# 0_3d.net
KiCad netlist of a schematic drawn in EAGLE
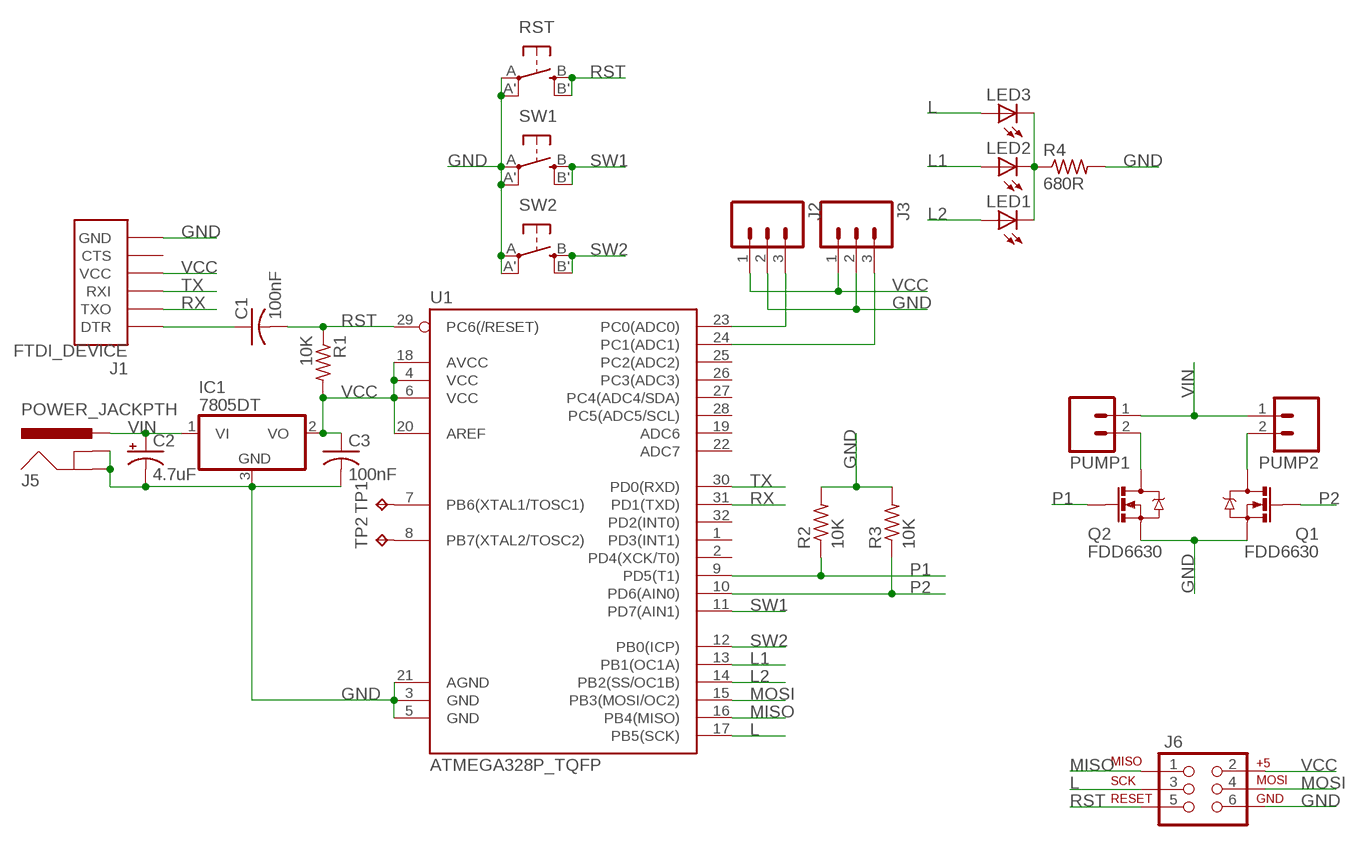
[diagram p0: schematic, sheet 1]

(export (version "E")
  (design (tool "Eeschema 10.0.6"))
  (components
    (comp (ref "C1")
      (value "100nF")
      (footprint "eagle-import:C1206K")
      (libsource (lib "eagle-import") (part "resistor_C-USC1206K"))
    )
    (comp (ref "C2")
      (value "4.7uF")
      (footprint "eagle-import:153CLV-0405")
      (libsource (lib "eagle-import") (part "CPOL-US153CLV-0405"))
    )
    (comp (ref "C3")
      (value "100nF")
      (footprint "eagle-import:C1206K")
      (libsource (lib "eagle-import") (part "C-USC1206K"))
    )
    (comp (ref "IC1")
      (value "7805DT")
      (footprint "eagle-import:TO252")
      (libsource (lib "eagle-import") (part "78DT05"))
    )
    (comp (ref "J1")
      (value "FTDI_DEVICE")
      (footprint "eagle-import:FTDI_DEVICE_SIDE")
      (libsource (lib "eagle-import") (part "FTDI_DEVICE"))
    )
    (comp (ref "J2")
      (value "M03PTH")
      (footprint "eagle-import:1X03")
      (libsource (lib "eagle-import") (part "M03PTH"))
    )
    (comp (ref "J3")
      (value "M03PTH")
      (footprint "eagle-import:1X03")
      (libsource (lib "eagle-import") (part "M03PTH"))
    )
    (comp (ref "J5")
      (value "POWER_JACKPTH")
      (footprint "eagle-import:POWER_JACK_PTH")
      (libsource (lib "eagle-import") (part "POWER_JACKPTH"))
    )
    (comp (ref "J6")
      (value "AVR_SPI_PRG_6PTH")
      (footprint "eagle-import:2X3")
      (libsource (lib "eagle-import") (part "AVR_SPI_PRG_6PTH"))
    )
    (comp (ref "LED1")
      (value "LED3MM")
      (footprint "eagle-import:LED3MM")
      (libsource (lib "eagle-import") (part "LED3MM"))
    )
    (comp (ref "LED2")
      (value "LED3MM")
      (footprint "eagle-import:LED3MM")
      (libsource (lib "eagle-import") (part "LED3MM"))
    )
    (comp (ref "LED3")
      (value "LED3MM")
      (footprint "eagle-import:LED3MM")
      (libsource (lib "eagle-import") (part "LED3MM"))
    )
    (comp (ref "PUMP1")
      (value "M02PTH")
      (footprint "eagle-import:1X02")
      (libsource (lib "eagle-import") (part "M02PTH"))
    )
    (comp (ref "PUMP2")
      (value "M02PTH")
      (footprint "eagle-import:1X02")
      (libsource (lib "eagle-import") (part "M02PTH"))
    )
    (comp (ref "Q1")
      (value "FDD6630")
      (footprint "eagle-import:D-PAK_TO252AA")
      (libsource (lib "eagle-import") (part "MOSFET-NCHANNEL_D-PAK"))
    )
    (comp (ref "Q2")
      (value "FDD6630")
      (footprint "eagle-import:D-PAK_TO252AA")
      (libsource (lib "eagle-import") (part "MOSFET-NCHANNEL_D-PAK"))
    )
    (comp (ref "R1")
      (value "10K")
      (footprint "eagle-import:M0805")
      (libsource (lib "eagle-import") (part "R-US_M0805"))
    )
    (comp (ref "R2")
      (value "10K")
      (footprint "eagle-import:M0805")
      (libsource (lib "eagle-import") (part "R-US_M0805"))
    )
    (comp (ref "R3")
      (value "10K")
      (footprint "eagle-import:M0805")
      (libsource (lib "eagle-import") (part "R-US_M0805"))
    )
    (comp (ref "R4")
      (value "680R")
      (footprint "eagle-import:M0805")
      (libsource (lib "eagle-import") (part "R-US_M0805"))
    )
    (comp (ref "RST")
      (value "SPST_TACT-EVQQ2")
      (footprint "eagle-import:EVQ-Q2")
      (libsource (lib "eagle-import") (part "SPST_TACT-EVQQ2"))
    )
    (comp (ref "SW1")
      (value "SPST_TACT-EVQQ2")
      (footprint "eagle-import:EVQ-Q2")
      (libsource (lib "eagle-import") (part "SPST_TACT-EVQQ2"))
    )
    (comp (ref "SW2")
      (value "SPST_TACT-EVQQ2")
      (footprint "eagle-import:EVQ-Q2")
      (libsource (lib "eagle-import") (part "SPST_TACT-EVQQ2"))
    )
    (comp (ref "TP1")
      (value "TPTP15SQ")
      (footprint "eagle-import:TP15SQ")
      (libsource (lib "eagle-import") (part "TPTP15SQ"))
    )
    (comp (ref "TP2")
      (value "TPTP15SQ")
      (footprint "eagle-import:TP15SQ")
      (libsource (lib "eagle-import") (part "TPTP15SQ"))
    )
    (comp (ref "U1")
      (value "ATMEGA328P_TQFP")
      (footprint "eagle-import:TQFP32-08")
      (libsource (lib "eagle-import") (part "ATMEGA328P_TQFP"))
    )
  )
  (nets
    (net (code "1") (name "/GND") (class "Default")
      (node (ref "C2") (pin "-") (pinfunction "-_-") (pintype "passive"))
      (node (ref "C3") (pin "2") (pinfunction "2_2") (pintype "passive"))
      (node (ref "IC1") (pin "3") (pinfunction "GND_3") (pintype "passive"))
      (node (ref "J1") (pin "P$6") (pinfunction "GND_P$6") (pintype "bidirectional"))
      (node (ref "J2") (pin "2") (pinfunction "2_2") (pintype "passive"))
      (node (ref "J3") (pin "2") (pinfunction "2_2") (pintype "passive"))
      (node (ref "J5") (pin "GND") (pinfunction "GND_GND") (pintype "bidirectional"))
      (node (ref "J5") (pin "GNDBREAK") (pinfunction "GNDBREAK_GNDBREAK") (pintype "bidirectional"))
      (node (ref "J6") (pin "6") (pinfunction "6_6") (pintype "passive"))
      (node (ref "Q1") (pin "3") (pinfunction "S_3") (pintype "passive"))
      (node (ref "Q2") (pin "3") (pinfunction "S_3") (pintype "passive"))
      (node (ref "R2") (pin "2") (pinfunction "2_2") (pintype "passive"))
      (node (ref "R3") (pin "2") (pinfunction "2_2") (pintype "passive"))
      (node (ref "R4") (pin "2") (pinfunction "2_2") (pintype "passive"))
      (node (ref "RST") (pin "A") (pinfunction "P_A") (pintype "passive"))
      (node (ref "RST") (pin "A'") (pinfunction "P1_A'") (pintype "passive"))
      (node (ref "SW1") (pin "A") (pinfunction "P_A") (pintype "passive"))
      (node (ref "SW1") (pin "A'") (pinfunction "P1_A'") (pintype "passive"))
      (node (ref "SW2") (pin "A") (pinfunction "P_A") (pintype "passive"))
      (node (ref "SW2") (pin "A'") (pinfunction "P1_A'") (pintype "passive"))
      (node (ref "U1") (pin "21") (pinfunction "AGND_21") (pintype "bidirectional"))
      (node (ref "U1") (pin "3") (pinfunction "GND_3") (pintype "bidirectional"))
      (node (ref "U1") (pin "5") (pinfunction "GND_5") (pintype "bidirectional"))
    )
    (net (code "2") (name "/L") (class "Default")
      (node (ref "J6") (pin "3") (pinfunction "3_3") (pintype "passive"))
      (node (ref "LED3") (pin "A") (pinfunction "A_A") (pintype "passive"))
      (node (ref "U1") (pin "17") (pinfunction "PB5(SCK)_17") (pintype "bidirectional"))
    )
    (net (code "3") (name "/L1") (class "Default")
      (node (ref "LED2") (pin "A") (pinfunction "A_A") (pintype "passive"))
      (node (ref "U1") (pin "13") (pinfunction "PB1(OC1A)_13") (pintype "bidirectional"))
    )
    (net (code "4") (name "/L2") (class "Default")
      (node (ref "LED1") (pin "A") (pinfunction "A_A") (pintype "passive"))
      (node (ref "U1") (pin "14") (pinfunction "PB2(SS/OC1B)_14") (pintype "bidirectional"))
    )
    (net (code "5") (name "/MISO") (class "Default")
      (node (ref "J6") (pin "1") (pinfunction "1_1") (pintype "passive"))
      (node (ref "U1") (pin "16") (pinfunction "PB4(MISO)_16") (pintype "bidirectional"))
    )
    (net (code "6") (name "/MOSI") (class "Default")
      (node (ref "J6") (pin "4") (pinfunction "4_4") (pintype "passive"))
      (node (ref "U1") (pin "15") (pinfunction "PB3(MOSI/OC2)_15") (pintype "bidirectional"))
    )
    (net (code "7") (name "/P1") (class "Default")
      (node (ref "Q2") (pin "1") (pinfunction "G_1") (pintype "passive"))
      (node (ref "R2") (pin "1") (pinfunction "1_1") (pintype "passive"))
      (node (ref "U1") (pin "9") (pinfunction "PD5(T1)_9") (pintype "bidirectional"))
    )
    (net (code "8") (name "/P2") (class "Default")
      (node (ref "Q1") (pin "1") (pinfunction "G_1") (pintype "passive"))
      (node (ref "R3") (pin "1") (pinfunction "1_1") (pintype "passive"))
      (node (ref "U1") (pin "10") (pinfunction "PD6(AIN0)_10") (pintype "bidirectional"))
    )
    (net (code "9") (name "/RST") (class "Default")
      (node (ref "C1") (pin "2") (pinfunction "2_2") (pintype "passive"))
      (node (ref "J6") (pin "5") (pinfunction "5_5") (pintype "passive"))
      (node (ref "R1") (pin "1") (pinfunction "1_1") (pintype "passive"))
      (node (ref "RST") (pin "B") (pinfunction "S_B") (pintype "passive"))
      (node (ref "RST") (pin "B'") (pinfunction "S1_B'") (pintype "passive"))
      (node (ref "U1") (pin "29") (pinfunction "PC6(/RESET)_29") (pintype "bidirectional"))
    )
    (net (code "10") (name "/RX") (class "Default")
      (node (ref "J1") (pin "P$2") (pinfunction "TXO_P$2") (pintype "bidirectional"))
      (node (ref "U1") (pin "31") (pinfunction "PD1(TXD)_31") (pintype "bidirectional"))
    )
    (net (code "11") (name "/SW1") (class "Default")
      (node (ref "SW1") (pin "B") (pinfunction "S_B") (pintype "passive"))
      (node (ref "SW1") (pin "B'") (pinfunction "S1_B'") (pintype "passive"))
      (node (ref "U1") (pin "11") (pinfunction "PD7(AIN1)_11") (pintype "bidirectional"))
    )
    (net (code "12") (name "/SW2") (class "Default")
      (node (ref "SW2") (pin "B") (pinfunction "S_B") (pintype "passive"))
      (node (ref "SW2") (pin "B'") (pinfunction "S1_B'") (pintype "passive"))
      (node (ref "U1") (pin "12") (pinfunction "PB0(ICP)_12") (pintype "bidirectional"))
    )
    (net (code "13") (name "/TX") (class "Default")
      (node (ref "J1") (pin "P$3") (pinfunction "RXI_P$3") (pintype "bidirectional"))
      (node (ref "U1") (pin "30") (pinfunction "PD0(RXD)_30") (pintype "bidirectional"))
    )
    (net (code "14") (name "/VCC") (class "Default")
      (node (ref "C3") (pin "1") (pinfunction "1_1") (pintype "passive"))
      (node (ref "IC1") (pin "2") (pinfunction "VO_2") (pintype "passive"))
      (node (ref "J1") (pin "P$4") (pinfunction "VCC_P$4") (pintype "bidirectional"))
      (node (ref "J2") (pin "1") (pinfunction "1_1") (pintype "passive"))
      (node (ref "J3") (pin "1") (pinfunction "1_1") (pintype "passive"))
      (node (ref "J6") (pin "2") (pinfunction "2_2") (pintype "passive"))
      (node (ref "R1") (pin "2") (pinfunction "2_2") (pintype "passive"))
      (node (ref "U1") (pin "18") (pinfunction "AVCC_18") (pintype "bidirectional"))
      (node (ref "U1") (pin "20") (pinfunction "AREF_20") (pintype "bidirectional"))
      (node (ref "U1") (pin "4") (pinfunction "VCC_4") (pintype "bidirectional"))
      (node (ref "U1") (pin "6") (pinfunction "VCC_6") (pintype "bidirectional"))
    )
    (net (code "15") (name "/VIN") (class "Default")
      (node (ref "C2") (pin "+") (pinfunction "+_+") (pintype "passive"))
      (node (ref "IC1") (pin "1") (pinfunction "VI_1") (pintype "input"))
      (node (ref "J5") (pin "PWR") (pinfunction "PWR_PWR") (pintype "bidirectional"))
      (node (ref "PUMP1") (pin "1") (pinfunction "1_1") (pintype "passive"))
      (node (ref "PUMP2") (pin "1") (pinfunction "1_1") (pintype "passive"))
    )
    (net (code "16") (name "Net-(J1-DTR)") (class "Default")
      (node (ref "C1") (pin "1") (pinfunction "1_1") (pintype "passive"))
      (node (ref "J1") (pin "P$1") (pinfunction "DTR_P$1") (pintype "bidirectional"))
    )
    (net (code "17") (name "Net-(LED1-C)") (class "Default")
      (node (ref "LED1") (pin "K") (pinfunction "C_K") (pintype "passive"))
      (node (ref "LED2") (pin "K") (pinfunction "C_K") (pintype "passive"))
      (node (ref "LED3") (pin "K") (pinfunction "C_K") (pintype "passive"))
      (node (ref "R4") (pin "1") (pinfunction "1_1") (pintype "passive"))
    )
    (net (code "18") (name "Net-(Q1-D)") (class "Default")
      (node (ref "PUMP2") (pin "2") (pinfunction "2_2") (pintype "passive"))
      (node (ref "Q1") (pin "2") (pinfunction "D_2") (pintype "passive"))
    )
    (net (code "19") (name "Net-(Q2-D)") (class "Default")
      (node (ref "PUMP1") (pin "2") (pinfunction "2_2") (pintype "passive"))
      (node (ref "Q2") (pin "2") (pinfunction "D_2") (pintype "passive"))
    )
    (net (code "20") (name "Net-(U1-PB6(XTAL1{slash}TOSC1))") (class "Default")
      (node (ref "TP1") (pin "TP") (pinfunction "TP_TP") (pintype "input"))
      (node (ref "U1") (pin "7") (pinfunction "PB6(XTAL1/TOSC1)_7") (pintype "bidirectional"))
    )
    (net (code "21") (name "Net-(U1-PB7(XTAL2{slash}TOSC2))") (class "Default")
      (node (ref "TP2") (pin "TP") (pinfunction "TP_TP") (pintype "input"))
      (node (ref "U1") (pin "8") (pinfunction "PB7(XTAL2/TOSC2)_8") (pintype "bidirectional"))
    )
    (net (code "22") (name "Net-(U1-PC0(ADC0))") (class "Default")
      (node (ref "J2") (pin "3") (pinfunction "3_3") (pintype "passive"))
      (node (ref "U1") (pin "23") (pinfunction "PC0(ADC0)_23") (pintype "bidirectional"))
    )
    (net (code "23") (name "Net-(U1-PC1(ADC1))") (class "Default")
      (node (ref "J3") (pin "3") (pinfunction "3_3") (pintype "passive"))
      (node (ref "U1") (pin "24") (pinfunction "PC1(ADC1)_24") (pintype "bidirectional"))
    )
    (net (code "24") (name "unconnected-(J1-CTS-PadP$5)") (class "Default")
      (node (ref "J1") (pin "P$5") (pinfunction "CTS_P$5") (pintype "bidirectional"))
    )
    (net (code "25") (name "unconnected-(U1-ADC6-Pad19)") (class "Default")
      (node (ref "U1") (pin "19") (pinfunction "ADC6_19") (pintype "bidirectional"))
    )
    (net (code "26") (name "unconnected-(U1-ADC7-Pad22)") (class "Default")
      (node (ref "U1") (pin "22") (pinfunction "ADC7_22") (pintype "bidirectional"))
    )
    (net (code "27") (name "unconnected-(U1-PC2(ADC2)-Pad25)") (class "Default")
      (node (ref "U1") (pin "25") (pinfunction "PC2(ADC2)_25") (pintype "bidirectional"))
    )
    (net (code "28") (name "unconnected-(U1-PC3(ADC3)-Pad26)") (class "Default")
      (node (ref "U1") (pin "26") (pinfunction "PC3(ADC3)_26") (pintype "bidirectional"))
    )
    (net (code "29") (name "unconnected-(U1-PC4(ADC4{slash}SDA)-Pad27)") (class "Default")
      (node (ref "U1") (pin "27") (pinfunction "PC4(ADC4/SDA)_27") (pintype "bidirectional"))
    )
    (net (code "30") (name "unconnected-(U1-PC5(ADC5{slash}SCL)-Pad28)") (class "Default")
      (node (ref "U1") (pin "28") (pinfunction "PC5(ADC5/SCL)_28") (pintype "bidirectional"))
    )
    (net (code "31") (name "unconnected-(U1-PD2(INT0)-Pad32)") (class "Default")
      (node (ref "U1") (pin "32") (pinfunction "PD2(INT0)_32") (pintype "bidirectional"))
    )
    (net (code "32") (name "unconnected-(U1-PD3(INT1)-Pad1)") (class "Default")
      (node (ref "U1") (pin "1") (pinfunction "PD3(INT1)_1") (pintype "bidirectional"))
    )
    (net (code "33") (name "unconnected-(U1-PD4(XCK{slash}T0)-Pad2)") (class "Default")
      (node (ref "U1") (pin "2") (pinfunction "PD4(XCK/T0)_2") (pintype "bidirectional"))
    )
  )
)
